# 05_POWER_MCU_2.net
KiCad netlist of a schematic drawn in Altium Designer
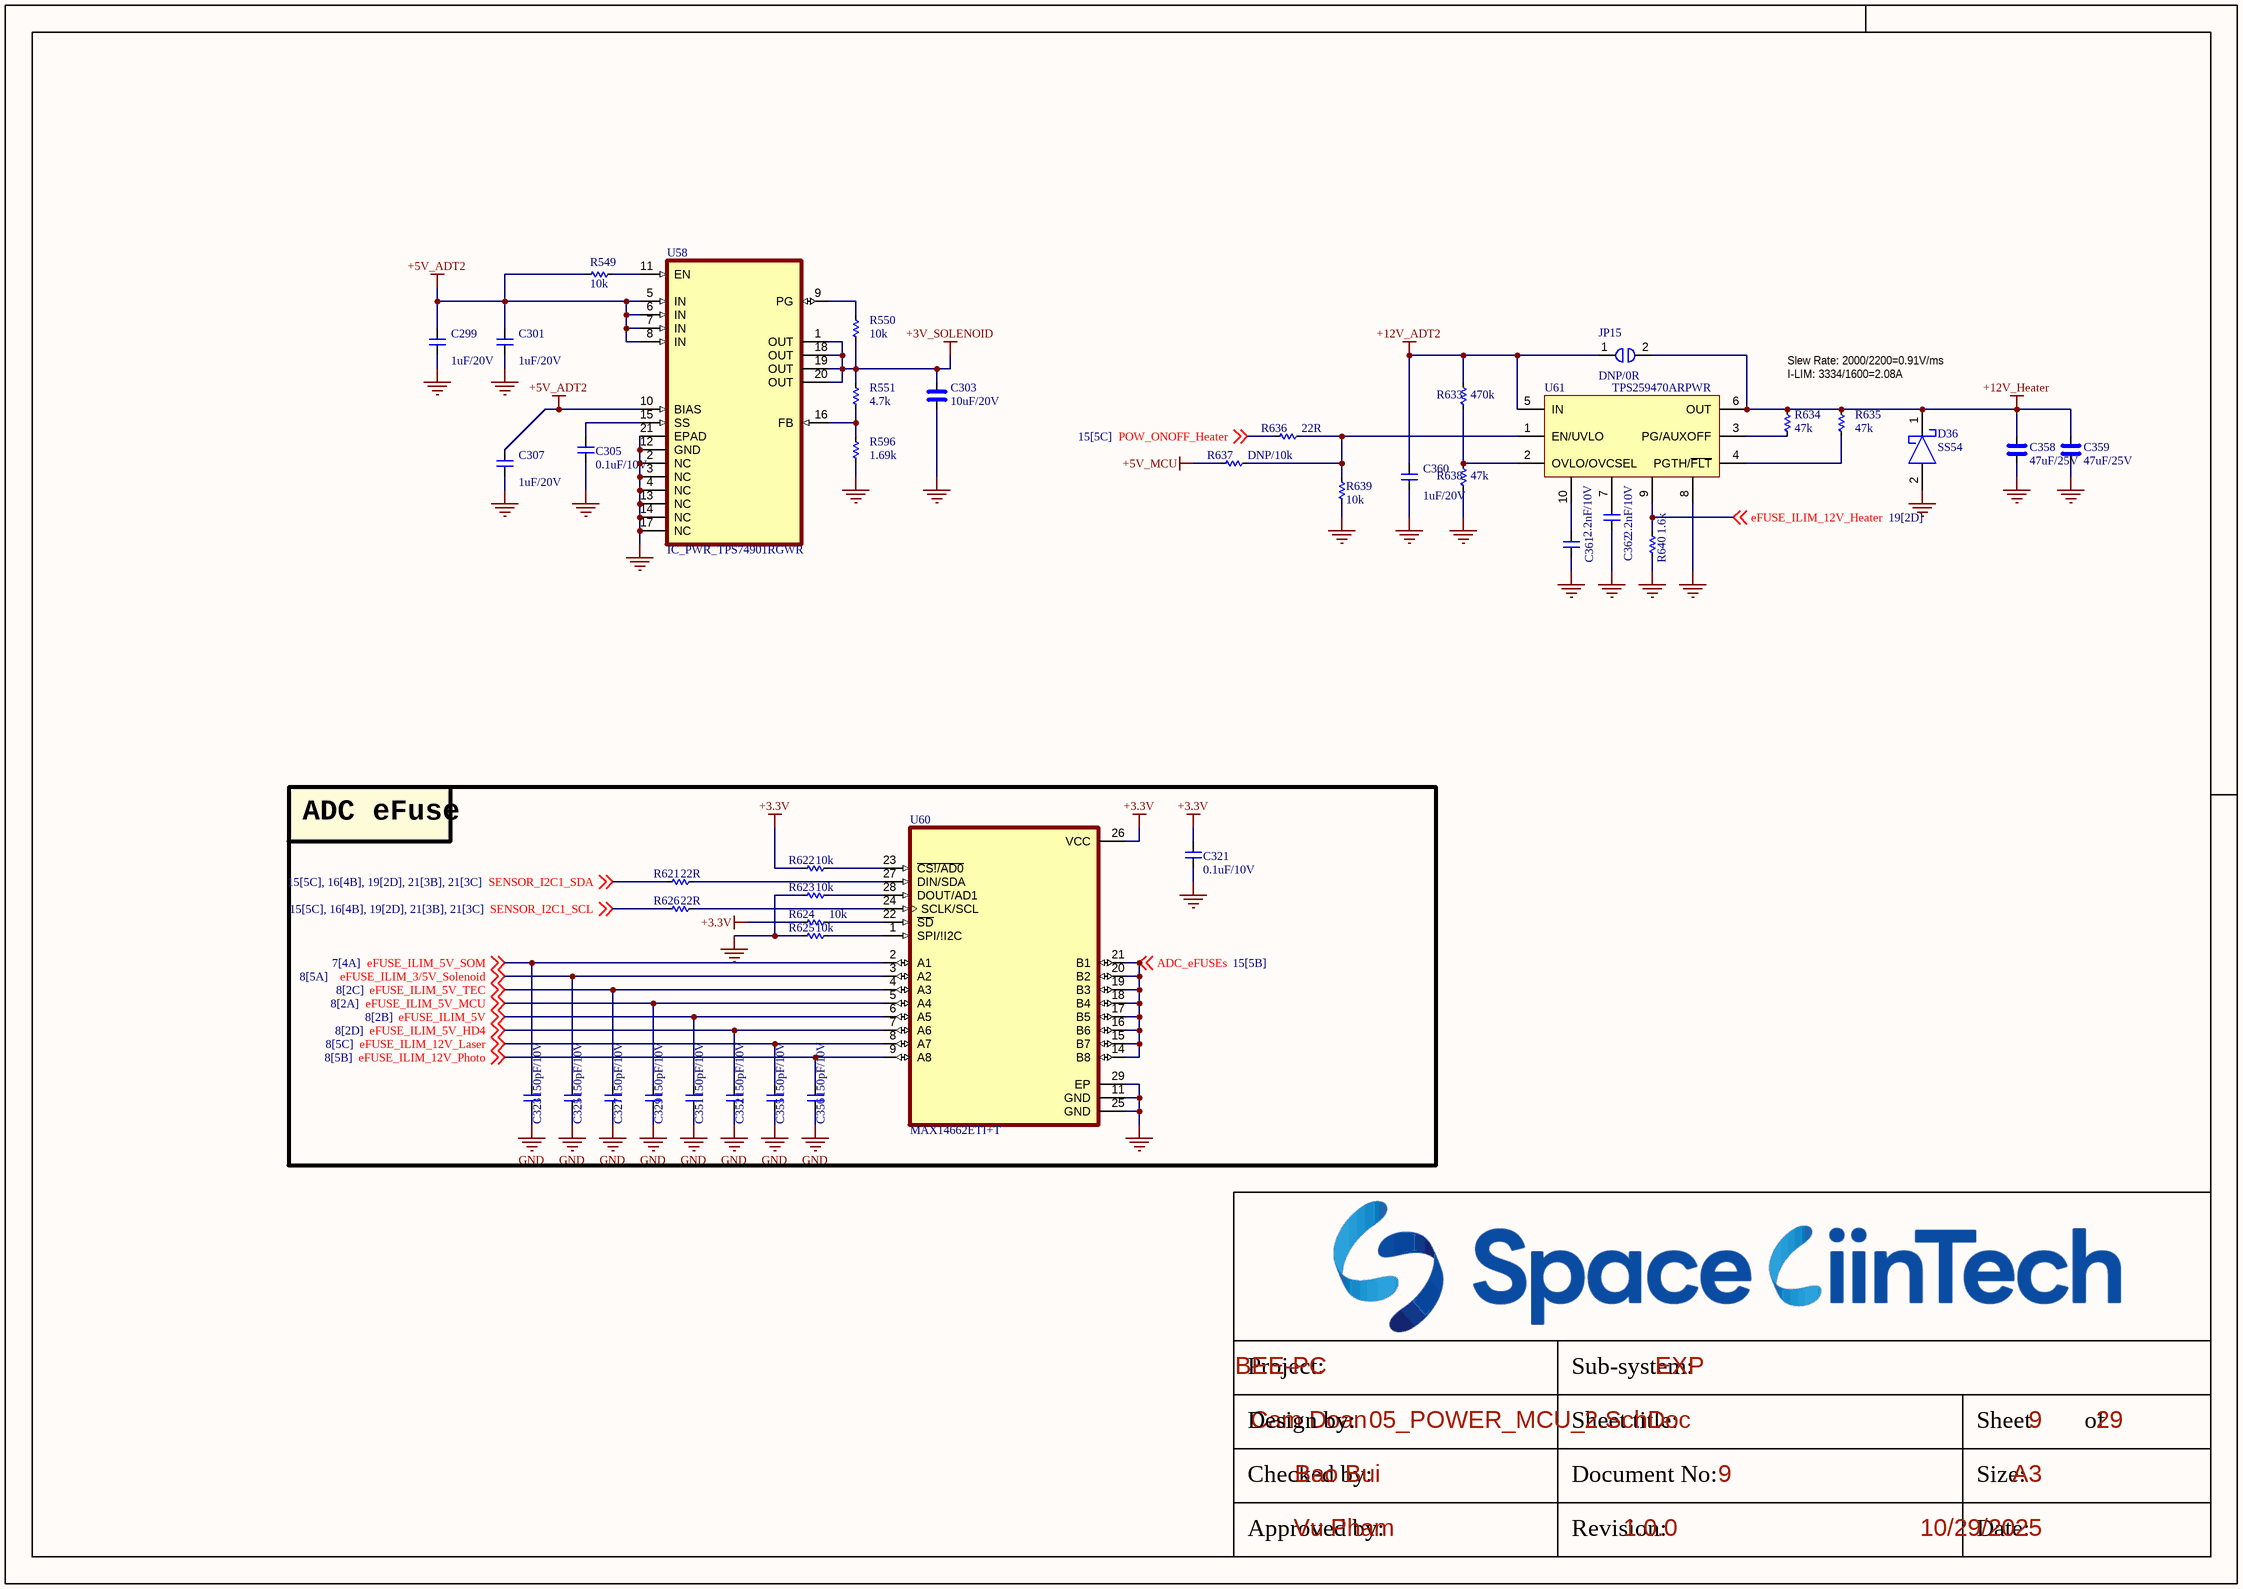
[diagram p0: 05_POWER_MCU_2.SchDoc]

(export (version "E")
  (design (tool "Eeschema 10.0.6"))
  (components
    (comp (ref "C299")
      (value "1uF/20V")
      (footprint "CAP_C_1005X60")
      (description "CAP CHIP")
      (libsource (lib "LABLIB") (part "_CAP_C_2"))
    )
    (comp (ref "C301")
      (value "1uF/20V")
      (footprint "CAP_C_1005X60")
      (description "CAP CHIP")
      (libsource (lib "LABLIB") (part "_CAP_C_2"))
    )
    (comp (ref "C303")
      (value "10uF/20V")
      (footprint "CAP_C_2012X110")
      (description "CAP CHIP High Value")
      (libsource (lib "LABLIB") (part "_CAP_C_High_2"))
    )
    (comp (ref "C305")
      (value "0.1uF/10V")
      (footprint "CAP_C_1005X60")
      (description "CAP CHIP")
      (libsource (lib "LABLIB") (part "_CAP_C_2"))
    )
    (comp (ref "C307")
      (value "1uF/20V")
      (footprint "CAP_C_1005X60")
      (description "CAP CHIP")
      (libsource (lib "LABLIB") (part "_CAP_C_2"))
    )
    (comp (ref "C321")
      (value "0.1uF/10V")
      (footprint "CAP_C_1005X60")
      (description "CAP CHIP")
      (libsource (lib "LABLIB") (part "_CAP_C_2"))
    )
    (comp (ref "C323")
      (value "150pF/10V")
      (footprint "CAP_C_1005X60")
      (description "CAP CHIP")
      (libsource (lib "LABLIB") (part "_CAP_C_2"))
    )
    (comp (ref "C325")
      (value "150pF/10V")
      (footprint "CAP_C_1005X60")
      (description "CAP CHIP")
      (libsource (lib "LABLIB") (part "_CAP_C_2"))
    )
    (comp (ref "C327")
      (value "150pF/10V")
      (footprint "CAP_C_1005X60")
      (description "CAP CHIP")
      (libsource (lib "LABLIB") (part "_CAP_C_2"))
    )
    (comp (ref "C329")
      (value "150pF/10V")
      (footprint "CAP_C_1005X60")
      (description "CAP CHIP")
      (libsource (lib "LABLIB") (part "_CAP_C_2"))
    )
    (comp (ref "C351")
      (value "150pF/10V")
      (footprint "CAP_C_1005X60")
      (description "CAP CHIP")
      (libsource (lib "LABLIB") (part "_CAP_C_2"))
    )
    (comp (ref "C352")
      (value "150pF/10V")
      (footprint "CAP_C_1005X60")
      (description "CAP CHIP")
      (libsource (lib "LABLIB") (part "_CAP_C_2"))
    )
    (comp (ref "C355")
      (value "150pF/10V")
      (footprint "CAP_C_1005X60")
      (description "CAP CHIP")
      (libsource (lib "LABLIB") (part "_CAP_C_2"))
    )
    (comp (ref "C356")
      (value "150pF/10V")
      (footprint "CAP_C_1005X60")
      (description "CAP CHIP")
      (libsource (lib "LABLIB") (part "_CAP_C_2"))
    )
    (comp (ref "C358")
      (value "47uF/25V")
      (footprint "CAP_C_3225X80")
      (description "CAP CHIP High Value")
      (libsource (lib "LABLIB") (part "_CAP_C_High_2"))
    )
    (comp (ref "C359")
      (value "47uF/25V")
      (footprint "CAP_C_3225X80")
      (description "CAP CHIP High Value")
      (libsource (lib "LABLIB") (part "_CAP_C_High_2"))
    )
    (comp (ref "C360")
      (value "1uF/20V")
      (footprint "CAP_C_1005X60")
      (description "CAP CHIP")
      (libsource (lib "LABLIB") (part "_CAP_C_2"))
    )
    (comp (ref "C361")
      (value "2.2nF/10V")
      (footprint "CAP_C_1005X60")
      (description "CAP CHIP")
      (libsource (lib "LABLIB") (part "_CAP_C_2"))
    )
    (comp (ref "C362")
      (value "2.2nF/10V")
      (footprint "CAP_C_1005X60")
      (description "CAP CHIP")
      (libsource (lib "LABLIB") (part "_CAP_C_2"))
    )
    (comp (ref "D36")
      (value "SS54")
      (footprint "DO-214AC_SMA")
      (description "DIODE SCHOTTKY 60V 3A DO214AA")
      (libsource (lib "EXP_HW_V3") (part "SS54"))
    )
    (comp (ref "JP15")
      (value "DNP/0R")
      (footprint "RES_C_1608X60")
      (libsource (lib "LABLIB") (part "JUMPER_1_1"))
    )
    (comp (ref "R549")
      (value "10k")
      (footprint "RES_C_1005X40")
      (description "RES")
      (libsource (lib "LABLIB") (part "_RES_B_2"))
    )
    (comp (ref "R550")
      (value "10k")
      (footprint "RES_C_1005X40")
      (description "RES")
      (libsource (lib "LABLIB") (part "_RES_B_2"))
    )
    (comp (ref "R551")
      (value "4.7k")
      (footprint "RES_C_1005X40")
      (description "RES")
      (libsource (lib "LABLIB") (part "_RES_B_2"))
    )
    (comp (ref "R596")
      (value "1.69k")
      (footprint "RES_C_1005X40")
      (description "RES")
      (libsource (lib "LABLIB") (part "_RES_B_2"))
    )
    (comp (ref "R621")
      (value "22R")
      (footprint "RES_C_1005X40")
      (description "RES")
      (libsource (lib "LABLIB") (part "_RES_B_2"))
    )
    (comp (ref "R622")
      (value "10k")
      (footprint "RES_C_1005X40")
      (description "RES")
      (libsource (lib "LABLIB") (part "_RES_B_2"))
    )
    (comp (ref "R623")
      (value "10k")
      (footprint "RES_C_1005X40")
      (description "RES")
      (libsource (lib "LABLIB") (part "_RES_B_2"))
    )
    (comp (ref "R624")
      (value "10k")
      (footprint "RES_C_1005X40")
      (description "RES")
      (libsource (lib "LABLIB") (part "_RES_B_2"))
    )
    (comp (ref "R625")
      (value "10k")
      (footprint "RES_C_1005X40")
      (description "RES")
      (libsource (lib "LABLIB") (part "_RES_B_2"))
    )
    (comp (ref "R626")
      (value "22R")
      (footprint "RES_C_1005X40")
      (description "RES")
      (libsource (lib "LABLIB") (part "_RES_B_2"))
    )
    (comp (ref "R633")
      (value "470k")
      (footprint "RES_C_1005X40")
      (description "RES")
      (libsource (lib "LABLIB") (part "_RES_B_2"))
    )
    (comp (ref "R634")
      (value "47k")
      (footprint "RES_C_1005X40")
      (description "RES")
      (libsource (lib "LABLIB") (part "_RES_B_2"))
    )
    (comp (ref "R635")
      (value "47k")
      (footprint "RES_C_1005X40")
      (description "RES")
      (libsource (lib "LABLIB") (part "_RES_B_2"))
    )
    (comp (ref "R636")
      (value "22R")
      (footprint "RES_C_1005X40")
      (description "RES")
      (libsource (lib "LABLIB") (part "_RES_B_2"))
    )
    (comp (ref "R637")
      (value "DNP/10k")
      (footprint "RES_C_1005X40")
      (description "RES")
      (libsource (lib "LABLIB") (part "_RES_B_2"))
    )
    (comp (ref "R638")
      (value "47k")
      (footprint "RES_C_1005X40")
      (description "RES")
      (libsource (lib "LABLIB") (part "_RES_B_2"))
    )
    (comp (ref "R639")
      (value "10k")
      (footprint "RES_C_1005X40")
      (description "RES")
      (libsource (lib "LABLIB") (part "_RES_B_2"))
    )
    (comp (ref "R640")
      (value "1.6k")
      (footprint "RES_C_1005X40")
      (description "RES")
      (libsource (lib "LABLIB") (part "_RES_B_2"))
    )
    (comp (ref "U58")
      (value "IC_PWR_TPS74901RGWR")
      (footprint "QFN65P500X500X100-21N:QFN65P500X500X100-21N")
      (fields (field (name "MF") "Texas Instruments") (field (name "MP") "TPS74901RGWR"))
      (libsource (lib "LABLIB") (part "IC_PWR_TPS74901RGWR"))
    )
    (comp (ref "U60")
      (value "MAX14662ETI+T")
      (footprint "QFN40P400X400X80-29N")
      (description "8 Circuit IC Switch 1:1 1Ohm 28-TQFN _4x4_")
      (fields (field (name "MF") "Maxim Integrated"))
      (libsource (lib "LABLIB") (part "IC_SW_MAX14662ETI+T"))
    )
    (comp (ref "U61")
      (value "TPS259470ARPWR")
      (footprint "VQFN-HR-10")
      (libsource (lib "EXP_HW_V3") (part "TPS259470ARPWR"))
    )
  )
  (nets
    (net (code "1") (name "+3.3V") (class "Default")
      (node (ref "C321") (pin "2") (pinfunction "2_2") (pintype "passive"))
      (node (ref "R622") (pin "1") (pinfunction "1_1") (pintype "passive"))
      (node (ref "R624") (pin "1") (pinfunction "1_1") (pintype "passive"))
      (node (ref "U60") (pin "26") (pinfunction "VCC_26") (pintype "power_in"))
    )
    (net (code "2") (name "+3V_SOLENOID") (class "Default")
      (node (ref "C303") (pin "1") (pinfunction "1_1") (pintype "passive"))
      (node (ref "R550") (pin "1") (pinfunction "1_1") (pintype "passive"))
      (node (ref "R551") (pin "2") (pinfunction "2_2") (pintype "passive"))
      (node (ref "U58") (pin "1") (pinfunction "OUT_1") (pintype "passive"))
      (node (ref "U58") (pin "18") (pinfunction "OUT_18") (pintype "passive"))
      (node (ref "U58") (pin "19") (pinfunction "OUT_19") (pintype "passive"))
      (node (ref "U58") (pin "20") (pinfunction "OUT_20") (pintype "passive"))
    )
    (net (code "3") (name "+5V_ADT2") (class "Default")
      (node (ref "C299") (pin "2") (pinfunction "2_2") (pintype "passive"))
      (node (ref "C301") (pin "2") (pinfunction "2_2") (pintype "passive"))
      (node (ref "C307") (pin "2") (pinfunction "2_2") (pintype "passive"))
      (node (ref "R549") (pin "2") (pinfunction "2_2") (pintype "passive"))
      (node (ref "U58") (pin "10") (pinfunction "BIAS_10") (pintype "input"))
      (node (ref "U58") (pin "5") (pinfunction "IN_5") (pintype "input"))
      (node (ref "U58") (pin "6") (pinfunction "IN_6") (pintype "input"))
      (node (ref "U58") (pin "7") (pinfunction "IN_7") (pintype "input"))
      (node (ref "U58") (pin "8") (pinfunction "IN_8") (pintype "input"))
    )
    (net (code "4") (name "+5V_MCU") (class "Default")
      (node (ref "R637") (pin "2") (pinfunction "2_2") (pintype "passive"))
    )
    (net (code "5") (name "+12V_ADT2") (class "Default")
      (node (ref "C360") (pin "2") (pinfunction "2_2") (pintype "passive"))
      (node (ref "JP15") (pin "1") (pinfunction "1_1") (pintype "passive"))
      (node (ref "R633") (pin "2") (pinfunction "2_2") (pintype "passive"))
      (node (ref "U61") (pin "5") (pinfunction "IN_5") (pintype "passive"))
    )
    (net (code "6") (name "+12V_Heater") (class "Default")
      (node (ref "C358") (pin "2") (pinfunction "2_2") (pintype "passive"))
      (node (ref "C359") (pin "2") (pinfunction "2_2") (pintype "passive"))
      (node (ref "D36") (pin "1") (pinfunction "1_1") (pintype "passive"))
      (node (ref "JP15") (pin "2") (pinfunction "2_2") (pintype "passive"))
      (node (ref "R634") (pin "2") (pinfunction "2_2") (pintype "passive"))
      (node (ref "R635") (pin "2") (pinfunction "2_2") (pintype "passive"))
      (node (ref "U61") (pin "6") (pinfunction "OUT_6") (pintype "passive"))
    )
    (net (code "7") (name "ADC_eFUSEs") (class "Default")
      (node (ref "U60") (pin "14") (pinfunction "B8_14") (pintype "bidirectional"))
      (node (ref "U60") (pin "15") (pinfunction "B7_15") (pintype "bidirectional"))
      (node (ref "U60") (pin "16") (pinfunction "B6_16") (pintype "bidirectional"))
      (node (ref "U60") (pin "17") (pinfunction "B5_17") (pintype "bidirectional"))
      (node (ref "U60") (pin "18") (pinfunction "B4_18") (pintype "bidirectional"))
      (node (ref "U60") (pin "19") (pinfunction "B3_19") (pintype "bidirectional"))
      (node (ref "U60") (pin "20") (pinfunction "B2_20") (pintype "bidirectional"))
      (node (ref "U60") (pin "21") (pinfunction "B1_21") (pintype "bidirectional"))
    )
    (net (code "8") (name "GND") (class "Default")
      (node (ref "C299") (pin "1") (pinfunction "1_1") (pintype "passive"))
      (node (ref "C301") (pin "1") (pinfunction "1_1") (pintype "passive"))
      (node (ref "C303") (pin "2") (pinfunction "2_2") (pintype "passive"))
      (node (ref "C305") (pin "1") (pinfunction "1_1") (pintype "passive"))
      (node (ref "C307") (pin "1") (pinfunction "1_1") (pintype "passive"))
      (node (ref "C321") (pin "1") (pinfunction "1_1") (pintype "passive"))
      (node (ref "C323") (pin "1") (pinfunction "1_1") (pintype "passive"))
      (node (ref "C325") (pin "1") (pinfunction "1_1") (pintype "passive"))
      (node (ref "C327") (pin "1") (pinfunction "1_1") (pintype "passive"))
      (node (ref "C329") (pin "1") (pinfunction "1_1") (pintype "passive"))
      (node (ref "C351") (pin "1") (pinfunction "1_1") (pintype "passive"))
      (node (ref "C352") (pin "1") (pinfunction "1_1") (pintype "passive"))
      (node (ref "C355") (pin "1") (pinfunction "1_1") (pintype "passive"))
      (node (ref "C356") (pin "1") (pinfunction "1_1") (pintype "passive"))
      (node (ref "C358") (pin "1") (pinfunction "1_1") (pintype "passive"))
      (node (ref "C359") (pin "1") (pinfunction "1_1") (pintype "passive"))
      (node (ref "C360") (pin "1") (pinfunction "1_1") (pintype "passive"))
      (node (ref "C361") (pin "1") (pinfunction "1_1") (pintype "passive"))
      (node (ref "C362") (pin "1") (pinfunction "1_1") (pintype "passive"))
      (node (ref "D36") (pin "2") (pinfunction "2_2") (pintype "passive"))
      (node (ref "R596") (pin "1") (pinfunction "1_1") (pintype "passive"))
      (node (ref "R623") (pin "1") (pinfunction "1_1") (pintype "passive"))
      (node (ref "R625") (pin "1") (pinfunction "1_1") (pintype "passive"))
      (node (ref "R638") (pin "1") (pinfunction "1_1") (pintype "passive"))
      (node (ref "R639") (pin "2") (pinfunction "2_2") (pintype "passive"))
      (node (ref "R640") (pin "1") (pinfunction "1_1") (pintype "passive"))
      (node (ref "U58") (pin "12") (pinfunction "GND_12") (pintype "power_in"))
      (node (ref "U58") (pin "13") (pinfunction "NC_13") (pintype "passive"))
      (node (ref "U58") (pin "14") (pinfunction "NC_14") (pintype "passive"))
      (node (ref "U58") (pin "17") (pinfunction "NC_17") (pintype "passive"))
      (node (ref "U58") (pin "2") (pinfunction "NC_2") (pintype "passive"))
      (node (ref "U58") (pin "21") (pinfunction "EPAD_21") (pintype "power_in"))
      (node (ref "U58") (pin "3") (pinfunction "NC_3") (pintype "passive"))
      (node (ref "U58") (pin "4") (pinfunction "NC_4") (pintype "passive"))
      (node (ref "U60") (pin "11") (pinfunction "GND_11") (pintype "power_in"))
      (node (ref "U60") (pin "25") (pinfunction "GND_25") (pintype "power_in"))
      (node (ref "U60") (pin "29") (pinfunction "EP_29") (pintype "power_in"))
      (node (ref "U61") (pin "8") (pinfunction "8_8") (pintype "passive"))
    )
    (net (code "9") (name "Net-(C361-Pad2)") (class "Default")
      (node (ref "C361") (pin "2") (pinfunction "2_2") (pintype "passive"))
      (node (ref "U61") (pin "10") (pinfunction "10_10") (pintype "passive"))
    )
    (net (code "10") (name "Net-(C362-Pad2)") (class "Default")
      (node (ref "C362") (pin "2") (pinfunction "2_2") (pintype "passive"))
      (node (ref "U61") (pin "7") (pinfunction "7_7") (pintype "passive"))
    )
    (net (code "11") (name "Net-(U58-EN)") (class "Default")
      (node (ref "R549") (pin "1") (pinfunction "1_1") (pintype "passive"))
      (node (ref "U58") (pin "11") (pinfunction "EN_11") (pintype "input"))
    )
    (net (code "12") (name "Net-(U58-FB)") (class "Default")
      (node (ref "R551") (pin "1") (pinfunction "1_1") (pintype "passive"))
      (node (ref "R596") (pin "2") (pinfunction "2_2") (pintype "passive"))
      (node (ref "U58") (pin "16") (pinfunction "FB_16") (pintype "input"))
    )
    (net (code "13") (name "Net-(U58-PG)") (class "Default")
      (node (ref "R550") (pin "2") (pinfunction "2_2") (pintype "passive"))
      (node (ref "U58") (pin "9") (pinfunction "PG_9") (pintype "bidirectional"))
    )
    (net (code "14") (name "Net-(U58-SS)") (class "Default")
      (node (ref "C305") (pin "2") (pinfunction "2_2") (pintype "passive"))
      (node (ref "U58") (pin "15") (pinfunction "SS_15") (pintype "input"))
    )
    (net (code "15") (name "Net-(U60-DIN{slash}SDA)") (class "Default")
      (node (ref "R621") (pin "2") (pinfunction "2_2") (pintype "passive"))
      (node (ref "U60") (pin "27") (pinfunction "DIN/SDA_27") (pintype "input"))
    )
    (net (code "16") (name "Net-(U60-DOUT{slash}AD1)") (class "Default")
      (node (ref "R623") (pin "2") (pinfunction "2_2") (pintype "passive"))
      (node (ref "U60") (pin "28") (pinfunction "DOUT/AD1_28") (pintype "input"))
    )
    (net (code "17") (name "Net-(U60-SCLK{slash}SCL)") (class "Default")
      (node (ref "R626") (pin "2") (pinfunction "2_2") (pintype "passive"))
      (node (ref "U60") (pin "24") (pinfunction "SCLK/SCL_24") (pintype "input"))
    )
    (net (code "18") (name "Net-(U60-SPI{slash}!I2C)") (class "Default")
      (node (ref "R625") (pin "2") (pinfunction "2_2") (pintype "passive"))
      (node (ref "U60") (pin "1") (pinfunction "SPI/!I2C_1") (pintype "input"))
    )
    (net (code "19") (name "Net-(U60-~{CS!{slash}AD0})") (class "Default")
      (node (ref "R622") (pin "2") (pinfunction "2_2") (pintype "passive"))
      (node (ref "U60") (pin "23") (pinfunction "~{CS!/AD0}_23") (pintype "input"))
    )
    (net (code "20") (name "Net-(U60-~{SD})") (class "Default")
      (node (ref "R624") (pin "2") (pinfunction "2_2") (pintype "passive"))
      (node (ref "U60") (pin "22") (pinfunction "~{SD}_22") (pintype "input"))
    )
    (net (code "21") (name "Net-(U61-EN{slash}UVLO)") (class "Default")
      (node (ref "R636") (pin "1") (pinfunction "1_1") (pintype "passive"))
      (node (ref "R637") (pin "1") (pinfunction "1_1") (pintype "passive"))
      (node (ref "R639") (pin "1") (pinfunction "1_1") (pintype "passive"))
      (node (ref "U61") (pin "1") (pinfunction "EN/UVLO_1") (pintype "passive"))
    )
    (net (code "22") (name "Net-(U61-OVLO{slash}OVCSEL)") (class "Default")
      (node (ref "R633") (pin "1") (pinfunction "1_1") (pintype "passive"))
      (node (ref "R638") (pin "2") (pinfunction "2_2") (pintype "passive"))
      (node (ref "U61") (pin "2") (pinfunction "OVLO/OVCSEL_2") (pintype "passive"))
    )
    (net (code "23") (name "Net-(U61-PGTH{slash}~{FLT})") (class "Default")
      (node (ref "R635") (pin "1") (pinfunction "1_1") (pintype "passive"))
      (node (ref "U61") (pin "4") (pinfunction "PGTH/~{FLT}_4") (pintype "passive"))
    )
    (net (code "24") (name "Net-(U61-PG{slash}AUXOFF)") (class "Default")
      (node (ref "R634") (pin "1") (pinfunction "1_1") (pintype "passive"))
      (node (ref "U61") (pin "3") (pinfunction "PG/AUXOFF_3") (pintype "passive"))
    )
    (net (code "25") (name "POW_ONOFF_Heater") (class "Default")
      (node (ref "R636") (pin "2") (pinfunction "2_2") (pintype "passive"))
    )
    (net (code "26") (name "SENSOR_I2C1_SCL") (class "Default")
      (node (ref "R626") (pin "1") (pinfunction "1_1") (pintype "passive"))
    )
    (net (code "27") (name "SENSOR_I2C1_SDA") (class "Default")
      (node (ref "R621") (pin "1") (pinfunction "1_1") (pintype "passive"))
    )
    (net (code "28") (name "eFUSE_ILIM_3{slash}5V_Solenoid") (class "Default")
      (node (ref "C325") (pin "2") (pinfunction "2_2") (pintype "passive"))
      (node (ref "U60") (pin "3") (pinfunction "A2_3") (pintype "bidirectional"))
    )
    (net (code "29") (name "eFUSE_ILIM_5V") (class "Default")
      (node (ref "C351") (pin "2") (pinfunction "2_2") (pintype "passive"))
      (node (ref "U60") (pin "6") (pinfunction "A5_6") (pintype "bidirectional"))
    )
    (net (code "30") (name "eFUSE_ILIM_5V_HD4") (class "Default")
      (node (ref "C352") (pin "2") (pinfunction "2_2") (pintype "passive"))
      (node (ref "U60") (pin "7") (pinfunction "A6_7") (pintype "bidirectional"))
    )
    (net (code "31") (name "eFUSE_ILIM_5V_MCU") (class "Default")
      (node (ref "C329") (pin "2") (pinfunction "2_2") (pintype "passive"))
      (node (ref "U60") (pin "5") (pinfunction "A4_5") (pintype "bidirectional"))
    )
    (net (code "32") (name "eFUSE_ILIM_5V_SOM") (class "Default")
      (node (ref "C323") (pin "2") (pinfunction "2_2") (pintype "passive"))
      (node (ref "U60") (pin "2") (pinfunction "A1_2") (pintype "bidirectional"))
    )
    (net (code "33") (name "eFUSE_ILIM_5V_TEC") (class "Default")
      (node (ref "C327") (pin "2") (pinfunction "2_2") (pintype "passive"))
      (node (ref "U60") (pin "4") (pinfunction "A3_4") (pintype "bidirectional"))
    )
    (net (code "34") (name "eFUSE_ILIM_12V_Heater") (class "Default")
      (node (ref "R640") (pin "2") (pinfunction "2_2") (pintype "passive"))
      (node (ref "U61") (pin "9") (pinfunction "9_9") (pintype "passive"))
    )
    (net (code "35") (name "eFUSE_ILIM_12V_Laser") (class "Default")
      (node (ref "C355") (pin "2") (pinfunction "2_2") (pintype "passive"))
      (node (ref "U60") (pin "8") (pinfunction "A7_8") (pintype "bidirectional"))
    )
    (net (code "36") (name "eFUSE_ILIM_12V_Photo") (class "Default")
      (node (ref "C356") (pin "2") (pinfunction "2_2") (pintype "passive"))
      (node (ref "U60") (pin "9") (pinfunction "A8_9") (pintype "bidirectional"))
    )
  )
)
